# PocketPilot.net
KiCad netlist of a schematic drawn in Altium Designer
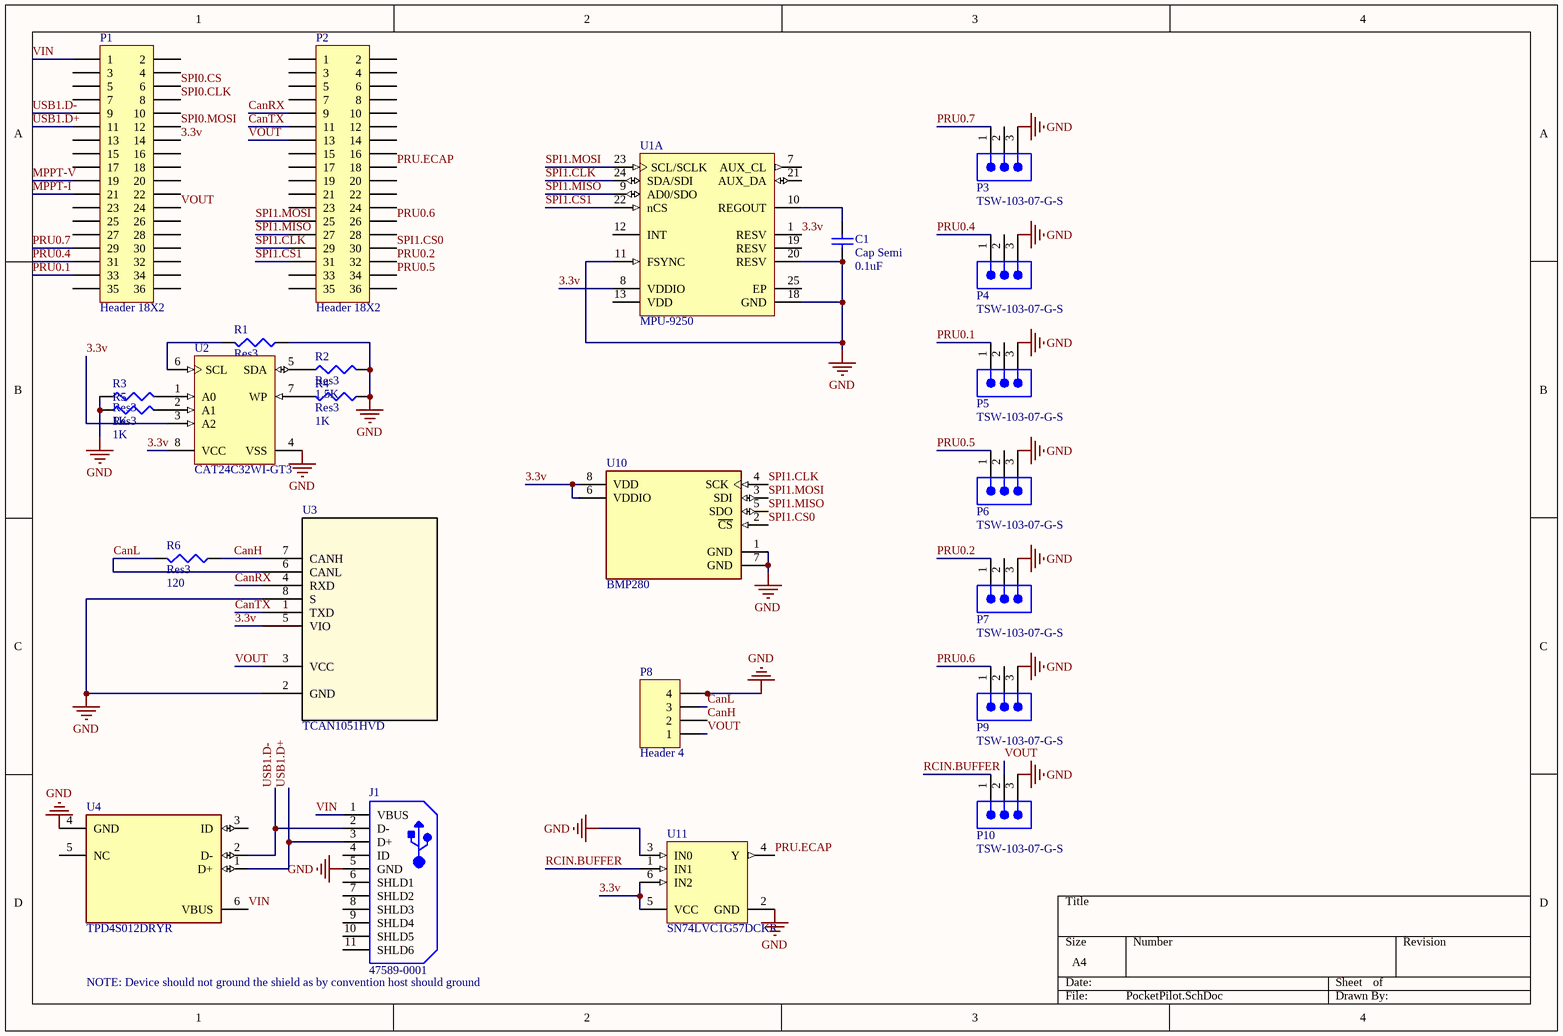
[diagram p0: PocketPilot.SchDoc]

(export (version "E")
  (design (tool "Eeschema 10.0.6"))
  (components
    (comp (ref "C1")
      (value "Cap Semi")
      (footprint "C1206")
      (description "Capacitor (Semiconductor SIM Model)")
      (fields (field (name "ALTIUM_VALUE") "0.1uF") (field (name "PUBLISHER") "Altium Limited"))
      (libsource (lib "Miscellaneous Devices") (part "Cap Semi"))
    )
    (comp (ref "J1")
      (value "47589-0001")
      (footprint "MOLX-47589-0001_V")
      (description "Right Angle Female Type AB Micro USB Connector, 30 V, 1.8 A, -30 to 85 degC, RoHS, Tape and Reel")
      (fields (field (name "MANUFACTURER") "Molex"))
      (libsource (lib "Altium Content Vault") (part "USB-5-6SHLD"))
    )
    (comp (ref "P1")
      (value "Header 18X2")
      (footprint "HDR2X18")
      (description "Header, 18-Pin, Dual row")
      (fields (field (name "PUBLISHER") "Altium Limited"))
      (libsource (lib "Miscellaneous Connectors") (part "Header 18X2"))
    )
    (comp (ref "P2")
      (value "Header 18X2")
      (footprint "HDR2X18")
      (description "Header, 18-Pin, Dual row")
      (fields (field (name "PUBLISHER") "Altium Limited"))
      (libsource (lib "Miscellaneous Connectors") (part "Header 18X2"))
    )
    (comp (ref "P3")
      (value "TSW-103-07-G-S")
      (footprint "SMTC-TSW-103-07-X-S")
      (description "0.025\" SQ Post Header, Through-hole, Vertical, -55 to 125 degC, 2.54 mm Pitch, 3-Pin, Male, RoHS")
      (fields (field (name "MANUFACTURER") "Samtec"))
      (libsource (lib "Altium Content Vault") (part "SMTC-TSW-103-X-X-S-X"))
    )
    (comp (ref "P4")
      (value "TSW-103-07-G-S")
      (footprint "SMTC-TSW-103-07-X-S")
      (description "0.025\" SQ Post Header, Through-hole, Vertical, -55 to 125 degC, 2.54 mm Pitch, 3-Pin, Male, RoHS")
      (fields (field (name "MANUFACTURER") "Samtec"))
      (libsource (lib "Altium Content Vault") (part "SMTC-TSW-103-X-X-S-X"))
    )
    (comp (ref "P5")
      (value "TSW-103-07-G-S")
      (footprint "SMTC-TSW-103-07-X-S")
      (description "0.025\" SQ Post Header, Through-hole, Vertical, -55 to 125 degC, 2.54 mm Pitch, 3-Pin, Male, RoHS")
      (fields (field (name "MANUFACTURER") "Samtec"))
      (libsource (lib "Altium Content Vault") (part "SMTC-TSW-103-X-X-S-X"))
    )
    (comp (ref "P6")
      (value "TSW-103-07-G-S")
      (footprint "SMTC-TSW-103-07-X-S")
      (description "0.025\" SQ Post Header, Through-hole, Vertical, -55 to 125 degC, 2.54 mm Pitch, 3-Pin, Male, RoHS")
      (fields (field (name "MANUFACTURER") "Samtec"))
      (libsource (lib "Altium Content Vault") (part "SMTC-TSW-103-X-X-S-X"))
    )
    (comp (ref "P7")
      (value "TSW-103-07-G-S")
      (footprint "SMTC-TSW-103-07-X-S")
      (description "0.025\" SQ Post Header, Through-hole, Vertical, -55 to 125 degC, 2.54 mm Pitch, 3-Pin, Male, RoHS")
      (fields (field (name "MANUFACTURER") "Samtec"))
      (libsource (lib "Altium Content Vault") (part "SMTC-TSW-103-X-X-S-X"))
    )
    (comp (ref "P8")
      (value "Header 4")
      (footprint "HDR1X4")
      (description "Header, 4-Pin")
      (fields (field (name "PUBLISHER") "Altium Limited"))
      (libsource (lib "Miscellaneous Connectors") (part "Header 4"))
    )
    (comp (ref "P9")
      (value "TSW-103-07-G-S")
      (footprint "SMTC-TSW-103-07-X-S")
      (description "0.025\" SQ Post Header, Through-hole, Vertical, -55 to 125 degC, 2.54 mm Pitch, 3-Pin, Male, RoHS")
      (fields (field (name "MANUFACTURER") "Samtec"))
      (libsource (lib "Altium Content Vault") (part "SMTC-TSW-103-X-X-S-X"))
    )
    (comp (ref "P10")
      (value "TSW-103-07-G-S")
      (footprint "SMTC-TSW-103-07-X-S")
      (description "0.025\" SQ Post Header, Through-hole, Vertical, -55 to 125 degC, 2.54 mm Pitch, 3-Pin, Male, RoHS")
      (fields (field (name "MANUFACTURER") "Samtec"))
      (libsource (lib "Altium Content Vault") (part "SMTC-TSW-103-X-X-S-X"))
    )
    (comp (ref "R1")
      (value "Res3")
      (footprint "J1-0603")
      (description "Resistor")
      (fields (field (name "ALTIUM_VALUE") "1.5K") (field (name "PUBLISHER") "Altium Limited"))
      (libsource (lib "Miscellaneous Devices") (part "Res3"))
    )
    (comp (ref "R2")
      (value "Res3")
      (footprint "J1-0603")
      (description "Resistor")
      (fields (field (name "ALTIUM_VALUE") "1.5K") (field (name "PUBLISHER") "Altium Limited"))
      (libsource (lib "Miscellaneous Devices") (part "Res3"))
    )
    (comp (ref "R3")
      (value "Res3")
      (footprint "J1-0603")
      (description "Resistor")
      (fields (field (name "ALTIUM_VALUE") "1K") (field (name "PUBLISHER") "Altium Limited"))
      (libsource (lib "Miscellaneous Devices") (part "Res3"))
    )
    (comp (ref "R4")
      (value "Res3")
      (footprint "J1-0603")
      (description "Resistor")
      (fields (field (name "ALTIUM_VALUE") "1K") (field (name "PUBLISHER") "Altium Limited"))
      (libsource (lib "Miscellaneous Devices") (part "Res3"))
    )
    (comp (ref "R5")
      (value "Res3")
      (footprint "J1-0603")
      (description "Resistor")
      (fields (field (name "ALTIUM_VALUE") "1K") (field (name "PUBLISHER") "Altium Limited"))
      (libsource (lib "Miscellaneous Devices") (part "Res3"))
    )
    (comp (ref "R6")
      (value "Res3")
      (footprint "J1-0603")
      (description "Resistor")
      (fields (field (name "ALTIUM_VALUE") "120") (field (name "PUBLISHER") "Altium Limited"))
      (libsource (lib "Miscellaneous Devices") (part "Res3"))
    )
    (comp (ref "U1")
      (value "MPU-9250")
      (footprint "INSE-QFN-24-1700X1540TP_M")
      (description "9-axis MotionTracking device, 2.4 to 3,6 V, -40 to 85 degC, 24-Pin QFN, RoHS, Tape and Reel")
      (fields (field (name "MANUFACTURER") "InvenSense"))
      (libsource (lib "Altium Content Vault") (part "INSE-MPU-9250-QFN-24"))
    )
    (comp (ref "U2")
      (value "CAT24C32WI-GT3")
      (footprint "ONSC-SOIC-8-751BD-01_M")
      (libsource (lib "Altium Content Vault") (part "ONSC-CAT24C32-SOIC-8"))
    )
    (comp (ref "U3")
      (value "TCAN1051HVD")
      (footprint "D8_TEX")
      (description "No Description Available")
      (fields (field (name "COPYRIGHT") "Copyright (C) 2018 Accelerated Designs. All rights reserved"))
      (libsource (lib "2021-03-15_04-22-52") (part "TCAN1051HVD"))
    )
    (comp (ref "U4")
      (value "TPD4S012DRYR")
      (footprint "FP-DRY0006A-MFG")
      (description "TVS DIODE 5.5V 6SON")
      (libsource (lib "Altium Content Vault") (part "0f51f1bc734c3fed0021f16fcfaf2e1"))
    )
    (comp (ref "U10")
      (value "BMP280")
      (footprint "FP-BMP280-MFG")
      (description "SENSOR PRESSURE ABS")
      (libsource (lib "Altium Content Vault") (part "69b1aacbb03d82763a43fac02afba64"))
    )
    (comp (ref "U11")
      (value "SN74LVC1G57DCKR")
      (footprint "DCK0006A_N")
      (description "CONFIGURABLE MULTIPLE-FUNCTION GATE, DCK0006A, LARGE T&R")
      (fields
        (field (name "GENERIC PART NUMBER") "SN74LVC1G57")
        (field (name "MANUFACTURER") "Texas Instruments")
      )
      (libsource (lib "Altium Content Vault") (part "TI-SN74XXX1GXX-6"))
    )
  )
  (nets
    (net (code "1") (name "/3.3v") (class "Default")
      (node (ref "P1") (pin "14") (pinfunction "14_14") (pintype "passive"))
      (node (ref "U1") (pin "1") (pinfunction "RESV_1") (pintype "power_in"))
      (node (ref "U1") (pin "8") (pinfunction "VDDIO_8") (pintype "power_in"))
      (node (ref "U10") (pin "6") (pinfunction "VDDIO_6") (pintype "power_in"))
      (node (ref "U10") (pin "8") (pinfunction "VDD_8") (pintype "power_in"))
      (node (ref "U11") (pin "5") (pinfunction "VCC_5") (pintype "power_in"))
      (node (ref "U11") (pin "6") (pinfunction "IN2_6") (pintype "input"))
      (node (ref "U2") (pin "3") (pinfunction "A2_3") (pintype "input"))
      (node (ref "U2") (pin "8") (pinfunction "VCC_8") (pintype "power_in"))
      (node (ref "U3") (pin "5") (pinfunction "VIO_5") (pintype "passive"))
    )
    (net (code "2") (name "/CanH") (class "Default")
      (node (ref "P8") (pin "2") (pinfunction "2_2") (pintype "passive"))
      (node (ref "R6") (pin "1") (pinfunction "1_1") (pintype "passive"))
      (node (ref "U3") (pin "7") (pinfunction "CANH_7") (pintype "passive"))
    )
    (net (code "3") (name "/CanL") (class "Default")
      (node (ref "P8") (pin "3") (pinfunction "3_3") (pintype "passive"))
      (node (ref "R6") (pin "2") (pinfunction "2_2") (pintype "passive"))
      (node (ref "U3") (pin "6") (pinfunction "CANL_6") (pintype "passive"))
    )
    (net (code "4") (name "/CanRX") (class "Default")
      (node (ref "P2") (pin "9") (pinfunction "9_9") (pintype "passive"))
      (node (ref "U3") (pin "4") (pinfunction "RXD_4") (pintype "passive"))
    )
    (net (code "5") (name "/CanTX") (class "Default")
      (node (ref "P2") (pin "11") (pinfunction "11_11") (pintype "passive"))
      (node (ref "U3") (pin "1") (pinfunction "TXD_1") (pintype "passive"))
    )
    (net (code "6") (name "/MPPT-I") (class "Default")
      (node (ref "P1") (pin "21") (pinfunction "21_21") (pintype "passive"))
    )
    (net (code "7") (name "/MPPT-V") (class "Default")
      (node (ref "P1") (pin "19") (pinfunction "19_19") (pintype "passive"))
    )
    (net (code "8") (name "/PRU.ECAP") (class "Default")
      (node (ref "P2") (pin "18") (pinfunction "18_18") (pintype "passive"))
      (node (ref "U11") (pin "4") (pinfunction "Y_4") (pintype "output"))
    )
    (net (code "9") (name "/PRU0.1") (class "Default")
      (node (ref "P1") (pin "33") (pinfunction "33_33") (pintype "passive"))
      (node (ref "P5") (pin "1") (pinfunction "1_1") (pintype "passive"))
    )
    (net (code "10") (name "/PRU0.2") (class "Default")
      (node (ref "P2") (pin "32") (pinfunction "32_32") (pintype "passive"))
      (node (ref "P7") (pin "1") (pinfunction "1_1") (pintype "passive"))
    )
    (net (code "11") (name "/PRU0.4") (class "Default")
      (node (ref "P1") (pin "31") (pinfunction "31_31") (pintype "passive"))
      (node (ref "P4") (pin "1") (pinfunction "1_1") (pintype "passive"))
    )
    (net (code "12") (name "/PRU0.5") (class "Default")
      (node (ref "P2") (pin "34") (pinfunction "34_34") (pintype "passive"))
      (node (ref "P6") (pin "1") (pinfunction "1_1") (pintype "passive"))
    )
    (net (code "13") (name "/PRU0.6") (class "Default")
      (node (ref "P2") (pin "26") (pinfunction "26_26") (pintype "passive"))
      (node (ref "P9") (pin "1") (pinfunction "1_1") (pintype "passive"))
    )
    (net (code "14") (name "/PRU0.7") (class "Default")
      (node (ref "P1") (pin "29") (pinfunction "29_29") (pintype "passive"))
      (node (ref "P3") (pin "1") (pinfunction "1_1") (pintype "passive"))
    )
    (net (code "15") (name "/RCIN.BUFFER") (class "Default")
      (node (ref "P10") (pin "1") (pinfunction "1_1") (pintype "passive"))
      (node (ref "U11") (pin "1") (pinfunction "IN1_1") (pintype "input"))
    )
    (net (code "16") (name "/SPI0.CLK") (class "Default")
      (node (ref "P1") (pin "8") (pinfunction "8_8") (pintype "passive"))
    )
    (net (code "17") (name "/SPI0.CS") (class "Default")
      (node (ref "P1") (pin "6") (pinfunction "6_6") (pintype "passive"))
    )
    (net (code "18") (name "/SPI0.MOSI") (class "Default")
      (node (ref "P1") (pin "12") (pinfunction "12_12") (pintype "passive"))
    )
    (net (code "19") (name "/SPI1.CLK") (class "Default")
      (node (ref "P2") (pin "29") (pinfunction "29_29") (pintype "passive"))
      (node (ref "U1") (pin "24") (pinfunction "SDA/SDI_24") (pintype "bidirectional"))
      (node (ref "U10") (pin "4") (pinfunction "SCK_4") (pintype "input"))
    )
    (net (code "20") (name "/SPI1.CS0") (class "Default")
      (node (ref "P2") (pin "30") (pinfunction "30_30") (pintype "passive"))
      (node (ref "U10") (pin "2") (pinfunction "~{CS}_2") (pintype "input"))
    )
    (net (code "21") (name "/SPI1.CS1") (class "Default")
      (node (ref "P2") (pin "31") (pinfunction "31_31") (pintype "passive"))
      (node (ref "U1") (pin "22") (pinfunction "nCS_22") (pintype "input"))
    )
    (net (code "22") (name "/SPI1.MISO") (class "Default")
      (node (ref "P2") (pin "27") (pinfunction "27_27") (pintype "passive"))
      (node (ref "U1") (pin "9") (pinfunction "AD0/SDO_9") (pintype "bidirectional"))
      (node (ref "U10") (pin "5") (pinfunction "SDO_5") (pintype "bidirectional"))
    )
    (net (code "23") (name "/SPI1.MOSI") (class "Default")
      (node (ref "P2") (pin "25") (pinfunction "25_25") (pintype "passive"))
      (node (ref "U1") (pin "23") (pinfunction "SCL/SCLK_23") (pintype "input"))
      (node (ref "U10") (pin "3") (pinfunction "SDI_3") (pintype "bidirectional"))
    )
    (net (code "24") (name "/USB1.D+") (class "Default")
      (node (ref "J1") (pin "3") (pinfunction "D+_3") (pintype "passive"))
      (node (ref "P1") (pin "11") (pinfunction "11_11") (pintype "passive"))
      (node (ref "U4") (pin "1") (pinfunction "D+_1") (pintype "bidirectional"))
    )
    (net (code "25") (name "/USB1.D-") (class "Default")
      (node (ref "J1") (pin "2") (pinfunction "D-_2") (pintype "passive"))
      (node (ref "P1") (pin "9") (pinfunction "9_9") (pintype "passive"))
      (node (ref "U4") (pin "2") (pinfunction "D-_2") (pintype "bidirectional"))
    )
    (net (code "26") (name "/VIN") (class "Default")
      (node (ref "J1") (pin "1") (pinfunction "VBUS_1") (pintype "passive"))
      (node (ref "P1") (pin "1") (pinfunction "1_1") (pintype "passive"))
      (node (ref "U4") (pin "6") (pinfunction "VBUS_6") (pintype "passive"))
    )
    (net (code "27") (name "/VOUT") (class "Default")
      (node (ref "P1") (pin "24") (pinfunction "24_24") (pintype "passive"))
      (node (ref "P10") (pin "2") (pinfunction "2_2") (pintype "passive"))
      (node (ref "P2") (pin "13") (pinfunction "13_13") (pintype "passive"))
      (node (ref "P8") (pin "1") (pinfunction "1_1") (pintype "passive"))
      (node (ref "U3") (pin "3") (pinfunction "VCC_3") (pintype "power_in"))
    )
    (net (code "28") (name "GND") (class "Default")
      (node (ref "C1") (pin "1") (pinfunction "1_1") (pintype "passive"))
      (node (ref "J1") (pin "5") (pinfunction "GND_5") (pintype "passive"))
      (node (ref "P10") (pin "3") (pinfunction "3_3") (pintype "passive"))
      (node (ref "P3") (pin "3") (pinfunction "3_3") (pintype "passive"))
      (node (ref "P4") (pin "3") (pinfunction "3_3") (pintype "passive"))
      (node (ref "P5") (pin "3") (pinfunction "3_3") (pintype "passive"))
      (node (ref "P6") (pin "3") (pinfunction "3_3") (pintype "passive"))
      (node (ref "P7") (pin "3") (pinfunction "3_3") (pintype "passive"))
      (node (ref "P8") (pin "4") (pinfunction "4_4") (pintype "passive"))
      (node (ref "P9") (pin "3") (pinfunction "3_3") (pintype "passive"))
      (node (ref "R1") (pin "1") (pinfunction "1_1") (pintype "passive"))
      (node (ref "R2") (pin "2") (pinfunction "2_2") (pintype "passive"))
      (node (ref "R3") (pin "1") (pinfunction "1_1") (pintype "passive"))
      (node (ref "R4") (pin "1") (pinfunction "1_1") (pintype "passive"))
      (node (ref "R5") (pin "1") (pinfunction "1_1") (pintype "passive"))
      (node (ref "U1") (pin "11") (pinfunction "FSYNC_11") (pintype "input"))
      (node (ref "U1") (pin "18") (pinfunction "GND_18") (pintype "power_in"))
      (node (ref "U1") (pin "20") (pinfunction "RESV_20") (pintype "power_in"))
      (node (ref "U10") (pin "1") (pinfunction "GND_1") (pintype "power_in"))
      (node (ref "U10") (pin "7") (pinfunction "GND_7") (pintype "power_in"))
      (node (ref "U11") (pin "2") (pinfunction "GND_2") (pintype "power_in"))
      (node (ref "U11") (pin "3") (pinfunction "IN0_3") (pintype "input"))
      (node (ref "U2") (pin "4") (pinfunction "VSS_4") (pintype "power_in"))
      (node (ref "U3") (pin "2") (pinfunction "GND_2") (pintype "passive"))
      (node (ref "U3") (pin "8") (pinfunction "S_8") (pintype "passive"))
      (node (ref "U4") (pin "4") (pinfunction "GND_4") (pintype "power_in"))
    )
    (net (code "29") (name "Net-(U1A-REGOUT)") (class "Default")
      (node (ref "C1") (pin "2") (pinfunction "2_2") (pintype "passive"))
      (node (ref "U1") (pin "10") (pinfunction "REGOUT_10") (pintype "passive"))
    )
    (net (code "30") (name "Net-(U2-A0)") (class "Default")
      (node (ref "R3") (pin "2") (pinfunction "2_2") (pintype "passive"))
      (node (ref "U2") (pin "1") (pinfunction "A0_1") (pintype "input"))
    )
    (net (code "31") (name "Net-(U2-A1)") (class "Default")
      (node (ref "R5") (pin "2") (pinfunction "2_2") (pintype "passive"))
      (node (ref "U2") (pin "2") (pinfunction "A1_2") (pintype "input"))
    )
    (net (code "32") (name "Net-(U2-SCL)") (class "Default")
      (node (ref "R1") (pin "2") (pinfunction "2_2") (pintype "passive"))
      (node (ref "U2") (pin "6") (pinfunction "SCL_6") (pintype "input"))
    )
    (net (code "33") (name "Net-(U2-SDA)") (class "Default")
      (node (ref "R2") (pin "1") (pinfunction "1_1") (pintype "passive"))
      (node (ref "U2") (pin "5") (pinfunction "SDA_5") (pintype "bidirectional"))
    )
    (net (code "34") (name "Net-(U2-WP)") (class "Default")
      (node (ref "R4") (pin "2") (pinfunction "2_2") (pintype "passive"))
      (node (ref "U2") (pin "7") (pinfunction "WP_7") (pintype "input"))
    )
    (net (code "35") (name "unconnected-(J1-ID-Pad4)") (class "Default")
      (node (ref "J1") (pin "4") (pinfunction "ID_4") (pintype "passive"))
    )
    (net (code "36") (name "unconnected-(J1-SHLD1-Pad6)") (class "Default")
      (node (ref "J1") (pin "6") (pinfunction "SHLD1_6") (pintype "passive"))
    )
    (net (code "37") (name "unconnected-(J1-SHLD2-Pad7)") (class "Default")
      (node (ref "J1") (pin "7") (pinfunction "SHLD2_7") (pintype "passive"))
    )
    (net (code "38") (name "unconnected-(J1-SHLD3-Pad8)") (class "Default")
      (node (ref "J1") (pin "8") (pinfunction "SHLD3_8") (pintype "passive"))
    )
    (net (code "39") (name "unconnected-(J1-SHLD4-Pad9)") (class "Default")
      (node (ref "J1") (pin "9") (pinfunction "SHLD4_9") (pintype "passive"))
    )
    (net (code "40") (name "unconnected-(J1-SHLD5-Pad10)") (class "Default")
      (node (ref "J1") (pin "10") (pinfunction "SHLD5_10") (pintype "passive"))
    )
    (net (code "41") (name "unconnected-(J1-SHLD6-Pad11)") (class "Default")
      (node (ref "J1") (pin "11") (pinfunction "SHLD6_11") (pintype "passive"))
    )
    (net (code "42") (name "unconnected-(P1-Pad2)") (class "Default")
      (node (ref "P1") (pin "2") (pinfunction "2_2") (pintype "passive"))
    )
    (net (code "43") (name "unconnected-(P1-Pad3)") (class "Default")
      (node (ref "P1") (pin "3") (pinfunction "3_3") (pintype "passive"))
    )
    (net (code "44") (name "unconnected-(P1-Pad4)") (class "Default")
      (node (ref "P1") (pin "4") (pinfunction "4_4") (pintype "passive"))
    )
    (net (code "45") (name "unconnected-(P1-Pad5)") (class "Default")
      (node (ref "P1") (pin "5") (pinfunction "5_5") (pintype "passive"))
    )
    (net (code "46") (name "unconnected-(P1-Pad7)") (class "Default")
      (node (ref "P1") (pin "7") (pinfunction "7_7") (pintype "passive"))
    )
    (net (code "47") (name "unconnected-(P1-Pad10)") (class "Default")
      (node (ref "P1") (pin "10") (pinfunction "10_10") (pintype "passive"))
    )
    (net (code "48") (name "unconnected-(P1-Pad13)") (class "Default")
      (node (ref "P1") (pin "13") (pinfunction "13_13") (pintype "passive"))
    )
    (net (code "49") (name "unconnected-(P1-Pad15)") (class "Default")
      (node (ref "P1") (pin "15") (pinfunction "15_15") (pintype "passive"))
    )
    (net (code "50") (name "unconnected-(P1-Pad16)") (class "Default")
      (node (ref "P1") (pin "16") (pinfunction "16_16") (pintype "passive"))
    )
    (net (code "51") (name "unconnected-(P1-Pad17)") (class "Default")
      (node (ref "P1") (pin "17") (pinfunction "17_17") (pintype "passive"))
    )
    (net (code "52") (name "unconnected-(P1-Pad18)") (class "Default")
      (node (ref "P1") (pin "18") (pinfunction "18_18") (pintype "passive"))
    )
    (net (code "53") (name "unconnected-(P1-Pad20)") (class "Default")
      (node (ref "P1") (pin "20") (pinfunction "20_20") (pintype "passive"))
    )
    (net (code "54") (name "unconnected-(P1-Pad22)") (class "Default")
      (node (ref "P1") (pin "22") (pinfunction "22_22") (pintype "passive"))
    )
    (net (code "55") (name "unconnected-(P1-Pad23)") (class "Default")
      (node (ref "P1") (pin "23") (pinfunction "23_23") (pintype "passive"))
    )
    (net (code "56") (name "unconnected-(P1-Pad25)") (class "Default")
      (node (ref "P1") (pin "25") (pinfunction "25_25") (pintype "passive"))
    )
    (net (code "57") (name "unconnected-(P1-Pad26)") (class "Default")
      (node (ref "P1") (pin "26") (pinfunction "26_26") (pintype "passive"))
    )
    (net (code "58") (name "unconnected-(P1-Pad27)") (class "Default")
      (node (ref "P1") (pin "27") (pinfunction "27_27") (pintype "passive"))
    )
    (net (code "59") (name "unconnected-(P1-Pad28)") (class "Default")
      (node (ref "P1") (pin "28") (pinfunction "28_28") (pintype "passive"))
    )
    (net (code "60") (name "unconnected-(P1-Pad30)") (class "Default")
      (node (ref "P1") (pin "30") (pinfunction "30_30") (pintype "passive"))
    )
    (net (code "61") (name "unconnected-(P1-Pad32)") (class "Default")
      (node (ref "P1") (pin "32") (pinfunction "32_32") (pintype "passive"))
    )
    (net (code "62") (name "unconnected-(P1-Pad34)") (class "Default")
      (node (ref "P1") (pin "34") (pinfunction "34_34") (pintype "passive"))
    )
    (net (code "63") (name "unconnected-(P1-Pad35)") (class "Default")
      (node (ref "P1") (pin "35") (pinfunction "35_35") (pintype "passive"))
    )
    (net (code "64") (name "unconnected-(P1-Pad36)") (class "Default")
      (node (ref "P1") (pin "36") (pinfunction "36_36") (pintype "passive"))
    )
    (net (code "65") (name "unconnected-(P2-Pad1)") (class "Default")
      (node (ref "P2") (pin "1") (pinfunction "1_1") (pintype "passive"))
    )
    (net (code "66") (name "unconnected-(P2-Pad2)") (class "Default")
      (node (ref "P2") (pin "2") (pinfunction "2_2") (pintype "passive"))
    )
    (net (code "67") (name "unconnected-(P2-Pad3)") (class "Default")
      (node (ref "P2") (pin "3") (pinfunction "3_3") (pintype "passive"))
    )
    (net (code "68") (name "unconnected-(P2-Pad4)") (class "Default")
      (node (ref "P2") (pin "4") (pinfunction "4_4") (pintype "passive"))
    )
    (net (code "69") (name "unconnected-(P2-Pad5)") (class "Default")
      (node (ref "P2") (pin "5") (pinfunction "5_5") (pintype "passive"))
    )
    (net (code "70") (name "unconnected-(P2-Pad6)") (class "Default")
      (node (ref "P2") (pin "6") (pinfunction "6_6") (pintype "passive"))
    )
    (net (code "71") (name "unconnected-(P2-Pad7)") (class "Default")
      (node (ref "P2") (pin "7") (pinfunction "7_7") (pintype "passive"))
    )
    (net (code "72") (name "unconnected-(P2-Pad8)") (class "Default")
      (node (ref "P2") (pin "8") (pinfunction "8_8") (pintype "passive"))
    )
    (net (code "73") (name "unconnected-(P2-Pad10)") (class "Default")
      (node (ref "P2") (pin "10") (pinfunction "10_10") (pintype "passive"))
    )
    (net (code "74") (name "unconnected-(P2-Pad12)") (class "Default")
      (node (ref "P2") (pin "12") (pinfunction "12_12") (pintype "passive"))
    )
    (net (code "75") (name "unconnected-(P2-Pad14)") (class "Default")
      (node (ref "P2") (pin "14") (pinfunction "14_14") (pintype "passive"))
    )
    (net (code "76") (name "unconnected-(P2-Pad15)") (class "Default")
      (node (ref "P2") (pin "15") (pinfunction "15_15") (pintype "passive"))
    )
    (net (code "77") (name "unconnected-(P2-Pad16)") (class "Default")
      (node (ref "P2") (pin "16") (pinfunction "16_16") (pintype "passive"))
    )
    (net (code "78") (name "unconnected-(P2-Pad17)") (class "Default")
      (node (ref "P2") (pin "17") (pinfunction "17_17") (pintype "passive"))
    )
    (net (code "79") (name "unconnected-(P2-Pad19)") (class "Default")
      (node (ref "P2") (pin "19") (pinfunction "19_19") (pintype "passive"))
    )
    (net (code "80") (name "unconnected-(P2-Pad20)") (class "Default")
      (node (ref "P2") (pin "20") (pinfunction "20_20") (pintype "passive"))
    )
    (net (code "81") (name "unconnected-(P2-Pad21)") (class "Default")
      (node (ref "P2") (pin "21") (pinfunction "21_21") (pintype "passive"))
    )
    (net (code "82") (name "unconnected-(P2-Pad22)") (class "Default")
      (node (ref "P2") (pin "22") (pinfunction "22_22") (pintype "passive"))
    )
    (net (code "83") (name "unconnected-(P2-Pad23)") (class "Default")
      (node (ref "P2") (pin "23") (pinfunction "23_23") (pintype "passive"))
    )
    (net (code "84") (name "unconnected-(P2-Pad24)") (class "Default")
      (node (ref "P2") (pin "24") (pinfunction "24_24") (pintype "passive"))
    )
    (net (code "85") (name "unconnected-(P2-Pad28)") (class "Default")
      (node (ref "P2") (pin "28") (pinfunction "28_28") (pintype "passive"))
    )
    (net (code "86") (name "unconnected-(P2-Pad33)") (class "Default")
      (node (ref "P2") (pin "33") (pinfunction "33_33") (pintype "passive"))
    )
    (net (code "87") (name "unconnected-(P2-Pad35)") (class "Default")
      (node (ref "P2") (pin "35") (pinfunction "35_35") (pintype "passive"))
    )
    (net (code "88") (name "unconnected-(P2-Pad36)") (class "Default")
      (node (ref "P2") (pin "36") (pinfunction "36_36") (pintype "passive"))
    )
    (net (code "89") (name "unconnected-(P3-Pad2)") (class "Default")
      (node (ref "P3") (pin "2") (pinfunction "2_2") (pintype "passive"))
    )
    (net (code "90") (name "unconnected-(P4-Pad2)") (class "Default")
      (node (ref "P4") (pin "2") (pinfunction "2_2") (pintype "passive"))
    )
    (net (code "91") (name "unconnected-(P5-Pad2)") (class "Default")
      (node (ref "P5") (pin "2") (pinfunction "2_2") (pintype "passive"))
    )
    (net (code "92") (name "unconnected-(P6-Pad2)") (class "Default")
      (node (ref "P6") (pin "2") (pinfunction "2_2") (pintype "passive"))
    )
    (net (code "93") (name "unconnected-(P7-Pad2)") (class "Default")
      (node (ref "P7") (pin "2") (pinfunction "2_2") (pintype "passive"))
    )
    (net (code "94") (name "unconnected-(P9-Pad2)") (class "Default")
      (node (ref "P9") (pin "2") (pinfunction "2_2") (pintype "passive"))
    )
    (net (code "95") (name "unconnected-(U1A-AUX_CL-Pad7)") (class "Default")
      (node (ref "U1") (pin "7") (pinfunction "AUX_CL_7") (pintype "output"))
    )
    (net (code "96") (name "unconnected-(U1A-AUX_DA-Pad21)") (class "Default")
      (node (ref "U1") (pin "21") (pinfunction "AUX_DA_21") (pintype "bidirectional"))
    )
    (net (code "97") (name "unconnected-(U1A-EP-Pad25)") (class "Default")
      (node (ref "U1") (pin "25") (pinfunction "EP_25") (pintype "passive"))
    )
    (net (code "98") (name "unconnected-(U1A-INT-Pad12)") (class "Default")
      (node (ref "U1") (pin "12") (pinfunction "INT_12") (pintype "tri_state"))
    )
    (net (code "99") (name "unconnected-(U1A-RESV-Pad19)") (class "Default")
      (node (ref "U1") (pin "19") (pinfunction "RESV_19") (pintype "passive"))
    )
    (net (code "100") (name "unconnected-(U1A-VDD-Pad13)") (class "Default")
      (node (ref "U1") (pin "13") (pinfunction "VDD_13") (pintype "power_in"))
    )
    (net (code "101") (name "unconnected-(U4-ID-Pad3)") (class "Default")
      (node (ref "U4") (pin "3") (pinfunction "ID_3") (pintype "bidirectional"))
    )
    (net (code "102") (name "unconnected-(U4-NC-Pad5)") (class "Default")
      (node (ref "U4") (pin "5") (pinfunction "NC_5") (pintype "passive"))
    )
  )
)
